# sheet_top.net
KiCad netlist of a schematic drawn in Altium Designer
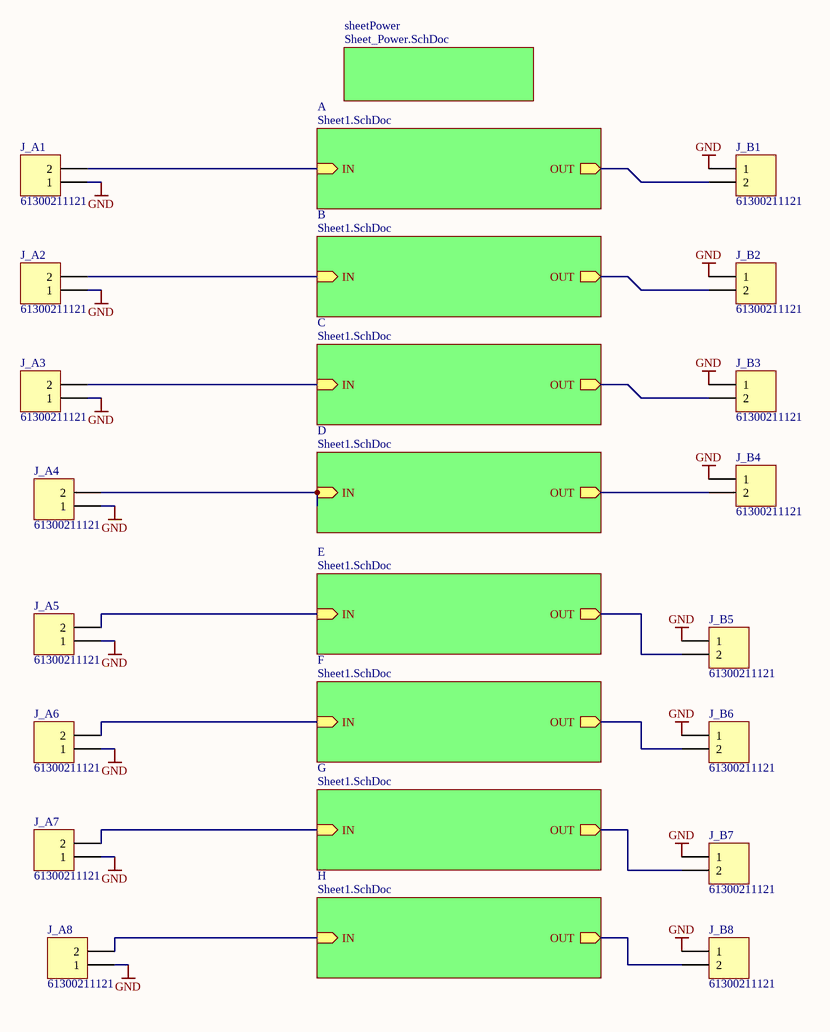
[diagram p0: sheet_top.SchDoc]

(export (version "E")
  (design (tool "Eeschema 10.0.6"))
  (components
    (comp (ref "J_A1")
      (value "61300211121")
      (footprint "61300211121")
      (description "2Pol; gerade; WR-PHD 2.54 mm THT Pin Header")
      (fields (field (name "MANUFACTURER") "Wurth Electronics"))
      (libsource (lib "Altium Vault EMBL 3") (part "CMP-001-0071-1"))
    )
    (comp (ref "J_A2")
      (value "61300211121")
      (footprint "61300211121")
      (description "2Pol; gerade; WR-PHD 2.54 mm THT Pin Header")
      (fields (field (name "MANUFACTURER") "Wurth Electronics"))
      (libsource (lib "Altium Vault EMBL 3") (part "CMP-001-0071-1"))
    )
    (comp (ref "J_A3")
      (value "61300211121")
      (footprint "61300211121")
      (description "2Pol; gerade; WR-PHD 2.54 mm THT Pin Header")
      (fields (field (name "MANUFACTURER") "Wurth Electronics"))
      (libsource (lib "Altium Vault EMBL 3") (part "CMP-001-0071-1"))
    )
    (comp (ref "J_A4")
      (value "61300211121")
      (footprint "61300211121")
      (description "2Pol; gerade; WR-PHD 2.54 mm THT Pin Header")
      (fields (field (name "MANUFACTURER") "Wurth Electronics"))
      (libsource (lib "Altium Vault EMBL 3") (part "CMP-001-0071-1"))
    )
    (comp (ref "J_A5")
      (value "61300211121")
      (footprint "61300211121")
      (description "2Pol; gerade; WR-PHD 2.54 mm THT Pin Header")
      (fields (field (name "MANUFACTURER") "Wurth Electronics"))
      (libsource (lib "Altium Vault EMBL 3") (part "CMP-001-0071-1"))
    )
    (comp (ref "J_A6")
      (value "61300211121")
      (footprint "61300211121")
      (description "2Pol; gerade; WR-PHD 2.54 mm THT Pin Header")
      (fields (field (name "MANUFACTURER") "Wurth Electronics"))
      (libsource (lib "Altium Vault EMBL 3") (part "CMP-001-0071-1"))
    )
    (comp (ref "J_A7")
      (value "61300211121")
      (footprint "61300211121")
      (description "2Pol; gerade; WR-PHD 2.54 mm THT Pin Header")
      (fields (field (name "MANUFACTURER") "Wurth Electronics"))
      (libsource (lib "Altium Vault EMBL 3") (part "CMP-001-0071-1"))
    )
    (comp (ref "J_A8")
      (value "61300211121")
      (footprint "61300211121")
      (description "2Pol; gerade; WR-PHD 2.54 mm THT Pin Header")
      (fields (field (name "MANUFACTURER") "Wurth Electronics"))
      (libsource (lib "Altium Vault EMBL 3") (part "CMP-001-0071-1"))
    )
    (comp (ref "J_B1")
      (value "61300211121")
      (footprint "61300211121")
      (description "2Pol; gerade; WR-PHD 2.54 mm THT Pin Header")
      (fields (field (name "MANUFACTURER") "Wurth Electronics"))
      (libsource (lib "Altium Vault EMBL 3") (part "61300211121"))
    )
    (comp (ref "J_B2")
      (value "61300211121")
      (footprint "61300211121")
      (description "2Pol; gerade; WR-PHD 2.54 mm THT Pin Header")
      (fields (field (name "MANUFACTURER") "Wurth Electronics"))
      (libsource (lib "") (part "CMP-001-0071-1_1"))
    )
    (comp (ref "J_B3")
      (value "61300211121")
      (footprint "61300211121")
      (description "2Pol; gerade; WR-PHD 2.54 mm THT Pin Header")
      (fields (field (name "MANUFACTURER") "Wurth Electronics"))
      (libsource (lib "") (part "CMP-001-0071-1_1"))
    )
    (comp (ref "J_B4")
      (value "61300211121")
      (footprint "61300211121")
      (description "2Pol; gerade; WR-PHD 2.54 mm THT Pin Header")
      (fields (field (name "MANUFACTURER") "Wurth Electronics"))
      (libsource (lib "") (part "CMP-001-0071-1_1"))
    )
    (comp (ref "J_B5")
      (value "61300211121")
      (footprint "61300211121")
      (description "2Pol; gerade; WR-PHD 2.54 mm THT Pin Header")
      (fields (field (name "MANUFACTURER") "Wurth Electronics"))
      (libsource (lib "") (part "CMP-001-0071-1_1"))
    )
    (comp (ref "J_B6")
      (value "61300211121")
      (footprint "61300211121")
      (description "2Pol; gerade; WR-PHD 2.54 mm THT Pin Header")
      (fields (field (name "MANUFACTURER") "Wurth Electronics"))
      (libsource (lib "") (part "CMP-001-0071-1_1"))
    )
    (comp (ref "J_B7")
      (value "61300211121")
      (footprint "61300211121")
      (description "2Pol; gerade; WR-PHD 2.54 mm THT Pin Header")
      (fields (field (name "MANUFACTURER") "Wurth Electronics"))
      (libsource (lib "") (part "CMP-001-0071-1_1"))
    )
    (comp (ref "J_B8")
      (value "61300211121")
      (footprint "61300211121")
      (description "2Pol; gerade; WR-PHD 2.54 mm THT Pin Header")
      (fields (field (name "MANUFACTURER") "Wurth Electronics"))
      (libsource (lib "") (part "CMP-001-0071-1_1"))
    )
  )
  (nets
    (net (code "1") (name "/IN") (class "Default")
      (node (ref "J_A3") (pin "2") (pinfunction "2_2") (pintype "passive"))
    )
    (net (code "2") (name "/IN_1") (class "Default")
      (node (ref "J_A7") (pin "2") (pinfunction "2_2") (pintype "passive"))
    )
    (net (code "3") (name "/IN_2") (class "Default")
      (node (ref "J_A8") (pin "2") (pinfunction "2_2") (pintype "passive"))
    )
    (net (code "4") (name "/IN_3") (class "Default")
      (node (ref "J_A4") (pin "2") (pinfunction "2_2") (pintype "passive"))
    )
    (net (code "5") (name "/IN_4") (class "Default")
      (node (ref "J_A5") (pin "2") (pinfunction "2_2") (pintype "passive"))
    )
    (net (code "6") (name "/IN_5") (class "Default")
      (node (ref "J_A6") (pin "2") (pinfunction "2_2") (pintype "passive"))
    )
    (net (code "7") (name "/IN_6") (class "Default")
      (node (ref "J_A1") (pin "2") (pinfunction "2_2") (pintype "passive"))
    )
    (net (code "8") (name "/IN_7") (class "Default")
      (node (ref "J_A2") (pin "2") (pinfunction "2_2") (pintype "passive"))
    )
    (net (code "9") (name "/OUT") (class "Default")
      (node (ref "J_B1") (pin "2") (pinfunction "2_2") (pintype "passive"))
    )
    (net (code "10") (name "/OUT_1") (class "Default")
      (node (ref "J_B8") (pin "2") (pinfunction "2_2") (pintype "passive"))
    )
    (net (code "11") (name "/OUT_2") (class "Default")
      (node (ref "J_B7") (pin "2") (pinfunction "2_2") (pintype "passive"))
    )
    (net (code "12") (name "/OUT_3") (class "Default")
      (node (ref "J_B4") (pin "2") (pinfunction "2_2") (pintype "passive"))
    )
    (net (code "13") (name "/OUT_4") (class "Default")
      (node (ref "J_B5") (pin "2") (pinfunction "2_2") (pintype "passive"))
    )
    (net (code "14") (name "/OUT_5") (class "Default")
      (node (ref "J_B6") (pin "2") (pinfunction "2_2") (pintype "passive"))
    )
    (net (code "15") (name "/OUT_6") (class "Default")
      (node (ref "J_B3") (pin "2") (pinfunction "2_2") (pintype "passive"))
    )
    (net (code "16") (name "/OUT_7") (class "Default")
      (node (ref "J_B2") (pin "2") (pinfunction "2_2") (pintype "passive"))
    )
    (net (code "17") (name "GND") (class "Default")
      (node (ref "J_A1") (pin "1") (pinfunction "1_1") (pintype "passive"))
      (node (ref "J_A2") (pin "1") (pinfunction "1_1") (pintype "passive"))
      (node (ref "J_A3") (pin "1") (pinfunction "1_1") (pintype "passive"))
      (node (ref "J_A4") (pin "1") (pinfunction "1_1") (pintype "passive"))
      (node (ref "J_A5") (pin "1") (pinfunction "1_1") (pintype "passive"))
      (node (ref "J_A6") (pin "1") (pinfunction "1_1") (pintype "passive"))
      (node (ref "J_A7") (pin "1") (pinfunction "1_1") (pintype "passive"))
      (node (ref "J_A8") (pin "1") (pinfunction "1_1") (pintype "passive"))
      (node (ref "J_B1") (pin "1") (pinfunction "1_1") (pintype "passive"))
      (node (ref "J_B2") (pin "1") (pinfunction "1_1") (pintype "passive"))
      (node (ref "J_B3") (pin "1") (pinfunction "1_1") (pintype "passive"))
      (node (ref "J_B4") (pin "1") (pinfunction "1_1") (pintype "passive"))
      (node (ref "J_B5") (pin "1") (pinfunction "1_1") (pintype "passive"))
      (node (ref "J_B6") (pin "1") (pinfunction "1_1") (pintype "passive"))
      (node (ref "J_B7") (pin "1") (pinfunction "1_1") (pintype "passive"))
      (node (ref "J_B8") (pin "1") (pinfunction "1_1") (pintype "passive"))
    )
  )
)
